# Power_Supply.net
KiCad netlist of a schematic drawn in Altium Designer
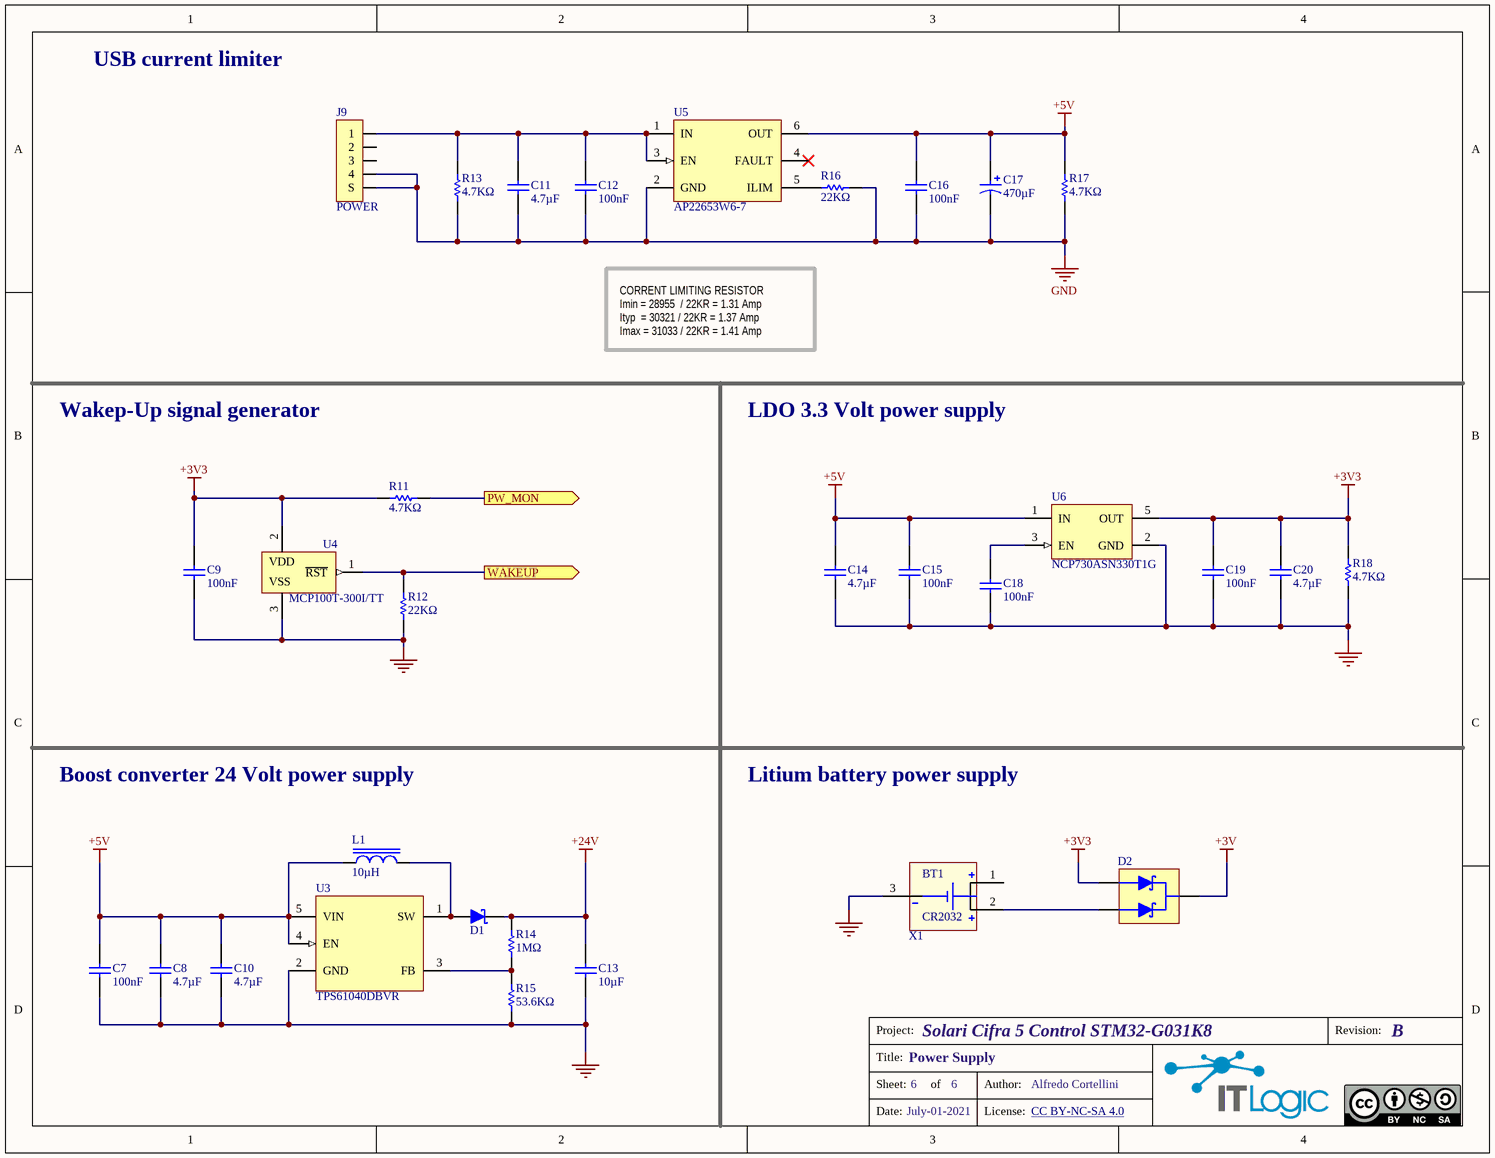
[diagram p0: Power Supply.SchDoc]

(export (version "E")
  (design (tool "Eeschema 10.0.6"))
  (components
    (comp (ref "BT1")
      (value "CR2032")
      (description "Battery Lithium 3V Coin 20mm")
      (fields (field (name "MANUFACTURER") "Panasonic BSG"))
      (libsource (lib "IT Logic Library") (part "CR2032"))
    )
    (comp (ref "C7")
      (value "100nF")
      (footprint "C0603-H90")
      (description "Cap 0603 Case Ceramic 100nF 50V X7R")
      (fields
        (field (name "MANUFACTURER") "TDK")
        (field (name "MANUFACTURER PART NUMBER") "CGA3E2X7R1H104K080AA")
      )
      (libsource (lib "IT Logic Library") (part "CGA3E2X7R1H104K080AA"))
    )
    (comp (ref "C8")
      (value "4.7µF")
      (footprint "C0603-H90")
      (description "Cap 0603 Case Ceramic 4.7uF 10V X7S")
      (fields
        (field (name "MANUFACTURER") "TDK")
        (field (name "MANUFACTURER PART NUMBER") "C1608X7S1A475K080AC")
      )
      (libsource (lib "IT Logic Library") (part "C1608X7S1A475K080AC"))
    )
    (comp (ref "C9")
      (value "100nF")
      (footprint "C0603-H90")
      (description "Cap 0603 Case Ceramic 100nF 50V X7R")
      (fields
        (field (name "MANUFACTURER") "TDK")
        (field (name "MANUFACTURER PART NUMBER") "CGA3E2X7R1H104K080AA")
      )
      (libsource (lib "IT Logic Library") (part "CGA3E2X7R1H104K080AA"))
    )
    (comp (ref "C10")
      (value "4.7µF")
      (footprint "C0603-H90")
      (description "Cap 0603 Case Ceramic 4.7uF 10V X7S")
      (fields
        (field (name "MANUFACTURER") "TDK")
        (field (name "MANUFACTURER PART NUMBER") "C1608X7S1A475K080AC")
      )
      (libsource (lib "IT Logic Library") (part "C1608X7S1A475K080AC"))
    )
    (comp (ref "C11")
      (value "4.7µF")
      (footprint "C0603-H90")
      (description "Cap 0603 Case Ceramic 4.7uF 10V X7S")
      (fields
        (field (name "MANUFACTURER") "TDK")
        (field (name "MANUFACTURER PART NUMBER") "C1608X7S1A475K080AC")
      )
      (libsource (lib "IT Logic Library") (part "C1608X7S1A475K080AC"))
    )
    (comp (ref "C12")
      (value "100nF")
      (footprint "C0603-H90")
      (description "Cap 0603 Case Ceramic 100nF 50V X7R")
      (fields
        (field (name "MANUFACTURER") "TDK")
        (field (name "MANUFACTURER PART NUMBER") "CGA3E2X7R1H104K080AA")
      )
      (libsource (lib "IT Logic Library") (part "CGA3E2X7R1H104K080AA"))
    )
    (comp (ref "C13")
      (value "10µF")
      (footprint "C1210-H250")
      (description "Cap 1210 Case Ceramic 10uF 50V X7R 10%")
      (fields
        (field (name "MANUFACTURER") "Samsung")
        (field (name "MANUFACTURER PART NUMBER") "CL32B106KBJNNWE")
      )
      (libsource (lib "IT Logic Library") (part "CL32B106KBJNNWE"))
    )
    (comp (ref "C14")
      (value "4.7µF")
      (footprint "C0603-H90")
      (description "Cap 0603 Case Ceramic 4.7uF 10V X7S")
      (fields
        (field (name "MANUFACTURER") "TDK")
        (field (name "MANUFACTURER PART NUMBER") "C1608X7S1A475K080AC")
      )
      (libsource (lib "IT Logic Library") (part "C1608X7S1A475K080AC"))
    )
    (comp (ref "C15")
      (value "100nF")
      (footprint "C0603-H90")
      (description "Cap 0603 Case Ceramic 100nF 50V X7R")
      (fields
        (field (name "MANUFACTURER") "TDK")
        (field (name "MANUFACTURER PART NUMBER") "CGA3E2X7R1H104K080AA")
      )
      (libsource (lib "IT Logic Library") (part "CGA3E2X7R1H104K080AA"))
    )
    (comp (ref "C16")
      (value "100nF")
      (footprint "C0603-H90")
      (description "Cap 0603 Case Ceramic 100nF 50V X7R")
      (fields
        (field (name "MANUFACTURER") "TDK")
        (field (name "MANUFACTURER PART NUMBER") "CGA3E2X7R1H104K080AA")
      )
      (libsource (lib "IT Logic Library") (part "CGA3E2X7R1H104K080AA"))
    )
    (comp (ref "C17")
      (value "470µF")
      (footprint "C-AE-D8-H102")
      (description "Cap Electrolytic Alu 470uF 16V 20% (10 X 10.2mm) SMD 600mA 2000h 105C Automotive T/R")
      (fields
        (field (name "MANUFACTURER") "Panasonic")
        (field (name "MANUFACTURER PART NUMBER") "EEE-FK1C471P")
      )
      (libsource (lib "IT Logic Library") (part "EEE-FK1C471P"))
    )
    (comp (ref "C18")
      (value "100nF")
      (footprint "C0603-H90")
      (description "Cap 0603 Case Ceramic 100nF 50V X7R")
      (fields
        (field (name "MANUFACTURER") "TDK")
        (field (name "MANUFACTURER PART NUMBER") "CGA3E2X7R1H104K080AA")
      )
      (libsource (lib "IT Logic Library") (part "CGA3E2X7R1H104K080AA"))
    )
    (comp (ref "C19")
      (value "100nF")
      (footprint "C0603-H90")
      (description "Cap 0603 Case Ceramic 100nF 50V X7R")
      (fields
        (field (name "MANUFACTURER") "TDK")
        (field (name "MANUFACTURER PART NUMBER") "CGA3E2X7R1H104K080AA")
      )
      (libsource (lib "IT Logic Library") (part "CGA3E2X7R1H104K080AA"))
    )
    (comp (ref "C20")
      (value "4.7µF")
      (footprint "C0603-H90")
      (description "Cap 0603 Case Ceramic 4.7uF 10V X7S")
      (fields
        (field (name "MANUFACTURER") "TDK")
        (field (name "MANUFACTURER PART NUMBER") "C1608X7S1A475K080AC")
      )
      (libsource (lib "IT Logic Library") (part "C1608X7S1A475K080AC"))
    )
    (comp (ref "D1")
      (value "ZLLS400QTC")
      (footprint "SOD-323")
      (description "Diode Schottky 40V 0.5A, Vf 480mV, 2-Pin SOD323")
      (fields (field (name "MANUFACTURER") "Diodes Incorporated"))
      (libsource (lib "IT Logic Library") (part "ZLLS400QTC"))
    )
    (comp (ref "D2")
      (value "BAT5405E6327HTSA1")
      (footprint "SOT-23")
      (description "Diode Schottky, Common cathode, 40V 0.3A 3-Pin SOT-323")
      (fields (field (name "MANUFACTURER") "Infineon Technologies"))
      (libsource (lib "IT Logic Library") (part "BAT5405E6327HTSA1"))
    )
    (comp (ref "J9")
      (value "POWER")
      (footprint "67068-8000")
      (description "Conn USB Type B Right-Angle, Kinked Solder Tabs")
      (fields (field (name "MANUFACTURER") "Molex") (field (name "MANUFACTURER PART NUMBER") "67068-8000"))
      (libsource (lib "IT Logic Library") (part "67068-8000"))
    )
    (comp (ref "L1")
      (value "10µH")
      (footprint "IND-LQH43CN")
      (description "Inductor Power LQH43CN Series, 10uH, 0.65 A, 0.24 ohm, SMD")
      (fields
        (field (name "MANUFACTURER") "Murata")
        (field (name "MANUFACTURER PART NUMBER") "LQH43CN100K03L")
      )
      (libsource (lib "IT Logic Library") (part "LQH43CN100K03L"))
    )
    (comp (ref "R11")
      (value "4.7KΩ")
      (footprint "R0603-H55")
      (description "Resistor 0603 Case 4.7KR 1% 1/10W")
      (fields
        (field (name "MANUFACTURER") "Yageo")
        (field (name "MANUFACTURER PART NUMBER") "RC0603FR-074K7L")
      )
      (libsource (lib "IT Logic Library") (part "RC0603FR-074K7L"))
    )
    (comp (ref "R12")
      (value "22KΩ")
      (footprint "R0603-H55")
      (description "Resistor 0603 Case 22KR 1% 1/10W")
      (fields
        (field (name "MANUFACTURER") "Yageo")
        (field (name "MANUFACTURER PART NUMBER") "RC0603FR-0722KL")
      )
      (libsource (lib "IT Logic Library") (part "RC0603FR-0722KL"))
    )
    (comp (ref "R13")
      (value "4.7KΩ")
      (footprint "R0603-H55")
      (description "Resistor 0603 Case 4.7KR 1% 1/10W")
      (fields
        (field (name "MANUFACTURER") "Yageo")
        (field (name "MANUFACTURER PART NUMBER") "RC0603FR-074K7L")
      )
      (libsource (lib "IT Logic Library") (part "RC0603FR-074K7L"))
    )
    (comp (ref "R14")
      (value "1MΩ")
      (footprint "R0603-H55")
      (description "Resistor 0603 Case 1MR 1% 1/10W")
      (fields
        (field (name "MANUFACTURER") "Yageo")
        (field (name "MANUFACTURER PART NUMBER") "RC0603FR-071ML")
      )
      (libsource (lib "IT Logic Library") (part "RC0603FR-071ML"))
    )
    (comp (ref "R15")
      (value "53.6KΩ")
      (footprint "R0603-H55")
      (description "Resistor 0603 Case 53.6KR 1% 1/10W")
      (fields
        (field (name "MANUFACTURER") "Yageo")
        (field (name "MANUFACTURER PART NUMBER") "RC0603FR-0753K6L")
      )
      (libsource (lib "IT Logic Library") (part "RC0603FR-0753K6L"))
    )
    (comp (ref "R16")
      (value "22KΩ")
      (footprint "R0603-H55")
      (description "Resistor 0603 Case 22KR 1% 1/10W")
      (fields
        (field (name "MANUFACTURER") "Yageo")
        (field (name "MANUFACTURER PART NUMBER") "RC0603FR-0722KL")
      )
      (libsource (lib "IT Logic Library") (part "RC0603FR-0722KL"))
    )
    (comp (ref "R17")
      (value "4.7KΩ")
      (footprint "R0603-H55")
      (description "Resistor 0603 Case 4.7KR 1% 1/10W")
      (fields
        (field (name "MANUFACTURER") "Yageo")
        (field (name "MANUFACTURER PART NUMBER") "RC0603FR-074K7L")
      )
      (libsource (lib "IT Logic Library") (part "RC0603FR-074K7L"))
    )
    (comp (ref "R18")
      (value "4.7KΩ")
      (footprint "R0603-H55")
      (description "Resistor 0603 Case 4.7KR 1% 1/10W")
      (fields
        (field (name "MANUFACTURER") "Yageo")
        (field (name "MANUFACTURER PART NUMBER") "RC0603FR-074K7L")
      )
      (libsource (lib "IT Logic Library") (part "RC0603FR-074K7L"))
    )
    (comp (ref "U3")
      (value "TPS61040DBVR")
      (footprint "SOT-235")
      (description "Conv DC-DC Sync Step-Up 28V .45A 1MHz SOT-23-5")
      (fields (field (name "MANUFACTURER") "Texas Instruments"))
      (libsource (lib "IT Logic Library") (part "TPS61040DBVR"))
    )
    (comp (ref "U4")
      (value "MCP100T-300I/TT")
      (footprint "SOT-23")
      (description "Power Supervisor 3.00V Low SOT23")
      (fields (field (name "MANUFACTURER") "Microchip"))
      (libsource (lib "IT Logic Library") (part "MCP100T-300I/TT"))
    )
    (comp (ref "U5")
      (value "AP22653W6-7")
      (footprint "SOT-236")
      (fields (field (name "MANUFACTURER") "Diodes Incorporated"))
      (libsource (lib "IT Logic Library") (part "AP22653W6-7"))
    )
    (comp (ref "U6")
      (value "NCP730ASN330T1G")
      (footprint "SOT-235")
      (description "LDO 3.3V 150mA Out  38Vin 290mV Dropout, Quiescent current 1 uA SOT-23-5")
      (fields (field (name "MANUFACTURER") "ON Semiconductor"))
      (libsource (lib "IT Logic Library") (part "NCP730ASN330T1G"))
    )
    (comp (ref "X1")
      (value "BAT-HLD-001")
      (footprint "BATT-TRAY-2032")
      (description "Holder Battery Coin 20mm")
      (fields (field (name "MANUFACTURER") "Linx"))
      (libsource (lib "IT Logic Library") (part "BAT-HLD-001"))
    )
  )
  (nets
    (net (code "1") (name "+3V") (class "Default")
      (node (ref "D2") (pin "3") (pinfunction "K_3") (pintype "passive"))
    )
    (net (code "2") (name "+3V3") (class "Default")
      (node (ref "C19") (pin "2") (pinfunction "2_2") (pintype "passive"))
      (node (ref "C20") (pin "2") (pinfunction "2_2") (pintype "passive"))
      (node (ref "C9") (pin "2") (pinfunction "2_2") (pintype "passive"))
      (node (ref "D2") (pin "1") (pinfunction "A_1") (pintype "passive"))
      (node (ref "R11") (pin "2") (pinfunction "2_2") (pintype "passive"))
      (node (ref "R18") (pin "2") (pinfunction "2_2") (pintype "passive"))
      (node (ref "U4") (pin "2") (pinfunction "VDD_2") (pintype "power_in"))
      (node (ref "U6") (pin "5") (pinfunction "OUT_5") (pintype "power_in"))
    )
    (net (code "3") (name "+5V") (class "Default")
      (node (ref "C10") (pin "2") (pinfunction "2_2") (pintype "passive"))
      (node (ref "C14") (pin "2") (pinfunction "2_2") (pintype "passive"))
      (node (ref "C15") (pin "2") (pinfunction "2_2") (pintype "passive"))
      (node (ref "C16") (pin "2") (pinfunction "2_2") (pintype "passive"))
      (node (ref "C17") (pin "1") (pinfunction "1_1") (pintype "passive"))
      (node (ref "C7") (pin "2") (pinfunction "2_2") (pintype "passive"))
      (node (ref "C8") (pin "2") (pinfunction "2_2") (pintype "passive"))
      (node (ref "L1") (pin "1") (pinfunction "1_1") (pintype "passive"))
      (node (ref "R17") (pin "2") (pinfunction "2_2") (pintype "passive"))
      (node (ref "U3") (pin "4") (pinfunction "EN_4") (pintype "input"))
      (node (ref "U3") (pin "5") (pinfunction "VIN_5") (pintype "power_in"))
      (node (ref "U5") (pin "6") (pinfunction "OUT_6") (pintype "power_in"))
      (node (ref "U6") (pin "1") (pinfunction "IN_1") (pintype "power_in"))
    )
    (net (code "4") (name "+24V") (class "Default")
      (node (ref "C13") (pin "2") (pinfunction "2_2") (pintype "passive"))
      (node (ref "D1") (pin "1") (pinfunction "K_1") (pintype "passive"))
      (node (ref "R14") (pin "2") (pinfunction "2_2") (pintype "passive"))
    )
    (net (code "5") (name "/PW_MON") (class "Default")
      (node (ref "R11") (pin "1") (pinfunction "1_1") (pintype "passive"))
    )
    (net (code "6") (name "/WAKEUP") (class "Default")
      (node (ref "R12") (pin "2") (pinfunction "2_2") (pintype "passive"))
      (node (ref "U4") (pin "1") (pinfunction "~{RST}_1") (pintype "output"))
    )
    (net (code "7") (name "GND") (class "Default")
      (node (ref "C10") (pin "1") (pinfunction "1_1") (pintype "passive"))
      (node (ref "C11") (pin "1") (pinfunction "1_1") (pintype "passive"))
      (node (ref "C12") (pin "1") (pinfunction "1_1") (pintype "passive"))
      (node (ref "C13") (pin "1") (pinfunction "1_1") (pintype "passive"))
      (node (ref "C14") (pin "1") (pinfunction "1_1") (pintype "passive"))
      (node (ref "C15") (pin "1") (pinfunction "1_1") (pintype "passive"))
      (node (ref "C16") (pin "1") (pinfunction "1_1") (pintype "passive"))
      (node (ref "C17") (pin "2") (pinfunction "2_2") (pintype "passive"))
      (node (ref "C18") (pin "1") (pinfunction "1_1") (pintype "passive"))
      (node (ref "C19") (pin "1") (pinfunction "1_1") (pintype "passive"))
      (node (ref "C20") (pin "1") (pinfunction "1_1") (pintype "passive"))
      (node (ref "C7") (pin "1") (pinfunction "1_1") (pintype "passive"))
      (node (ref "C8") (pin "1") (pinfunction "1_1") (pintype "passive"))
      (node (ref "C9") (pin "1") (pinfunction "1_1") (pintype "passive"))
      (node (ref "J9") (pin "4") (pinfunction "4_4") (pintype "passive"))
      (node (ref "J9") (pin "S") (pinfunction "S_S") (pintype "passive"))
      (node (ref "R12") (pin "1") (pinfunction "1_1") (pintype "passive"))
      (node (ref "R13") (pin "1") (pinfunction "1_1") (pintype "passive"))
      (node (ref "R15") (pin "1") (pinfunction "1_1") (pintype "passive"))
      (node (ref "R16") (pin "2") (pinfunction "2_2") (pintype "passive"))
      (node (ref "R17") (pin "1") (pinfunction "1_1") (pintype "passive"))
      (node (ref "R18") (pin "1") (pinfunction "1_1") (pintype "passive"))
      (node (ref "U3") (pin "2") (pinfunction "GND_2") (pintype "power_in"))
      (node (ref "U4") (pin "3") (pinfunction "VSS_3") (pintype "power_in"))
      (node (ref "U5") (pin "2") (pinfunction "GND_2") (pintype "power_in"))
      (node (ref "U6") (pin "2") (pinfunction "GND_2") (pintype "power_in"))
      (node (ref "X1") (pin "3") (pinfunction "-_3") (pintype "power_in"))
    )
    (net (code "8") (name "Net-(D1-A)") (class "Default")
      (node (ref "D1") (pin "2") (pinfunction "A_2") (pintype "passive"))
      (node (ref "L1") (pin "2") (pinfunction "2_2") (pintype "passive"))
      (node (ref "U3") (pin "1") (pinfunction "SW_1") (pintype "power_in"))
    )
    (net (code "9") (name "Net-(D2-A-Pad2)") (class "Default")
      (node (ref "D2") (pin "2") (pinfunction "A_2") (pintype "passive"))
      (node (ref "X1") (pin "2") (pinfunction "+_2") (pintype "power_in"))
    )
    (net (code "10") (name "Net-(U3-FB)") (class "Default")
      (node (ref "R14") (pin "1") (pinfunction "1_1") (pintype "passive"))
      (node (ref "R15") (pin "2") (pinfunction "2_2") (pintype "passive"))
      (node (ref "U3") (pin "3") (pinfunction "FB_3") (pintype "power_in"))
    )
    (net (code "11") (name "Net-(U5-EN)") (class "Default")
      (node (ref "C11") (pin "2") (pinfunction "2_2") (pintype "passive"))
      (node (ref "C12") (pin "2") (pinfunction "2_2") (pintype "passive"))
      (node (ref "J9") (pin "1") (pinfunction "1_1") (pintype "passive"))
      (node (ref "R13") (pin "2") (pinfunction "2_2") (pintype "passive"))
      (node (ref "U5") (pin "1") (pinfunction "IN_1") (pintype "power_in"))
      (node (ref "U5") (pin "3") (pinfunction "EN_3") (pintype "input"))
    )
    (net (code "12") (name "Net-(U5-ILIM)") (class "Default")
      (node (ref "R16") (pin "1") (pinfunction "1_1") (pintype "passive"))
      (node (ref "U5") (pin "5") (pinfunction "ILIM_5") (pintype "power_in"))
    )
    (net (code "13") (name "Net-(U6-EN)") (class "Default")
      (node (ref "C18") (pin "2") (pinfunction "2_2") (pintype "passive"))
      (node (ref "U6") (pin "3") (pinfunction "EN_3") (pintype "input"))
    )
    (net (code "14") (name "unconnected-(J9-Pad2)") (class "Default")
      (node (ref "J9") (pin "2") (pinfunction "2_2") (pintype "passive"))
    )
    (net (code "15") (name "unconnected-(J9-Pad3)") (class "Default")
      (node (ref "J9") (pin "3") (pinfunction "3_3") (pintype "passive"))
    )
    (net (code "16") (name "unconnected-(U5-FAULT-Pad4)") (class "Default")
      (node (ref "U5") (pin "4") (pinfunction "FAULT_4") (pintype "open_collector+no_connect"))
    )
    (net (code "17") (name "unconnected-(X1-+-Pad1)") (class "Default")
      (node (ref "X1") (pin "1") (pinfunction "+_1") (pintype "power_in"))
    )
  )
)
